# CR_Weather.net
KiCad netlist of a schematic drawn in EAGLE
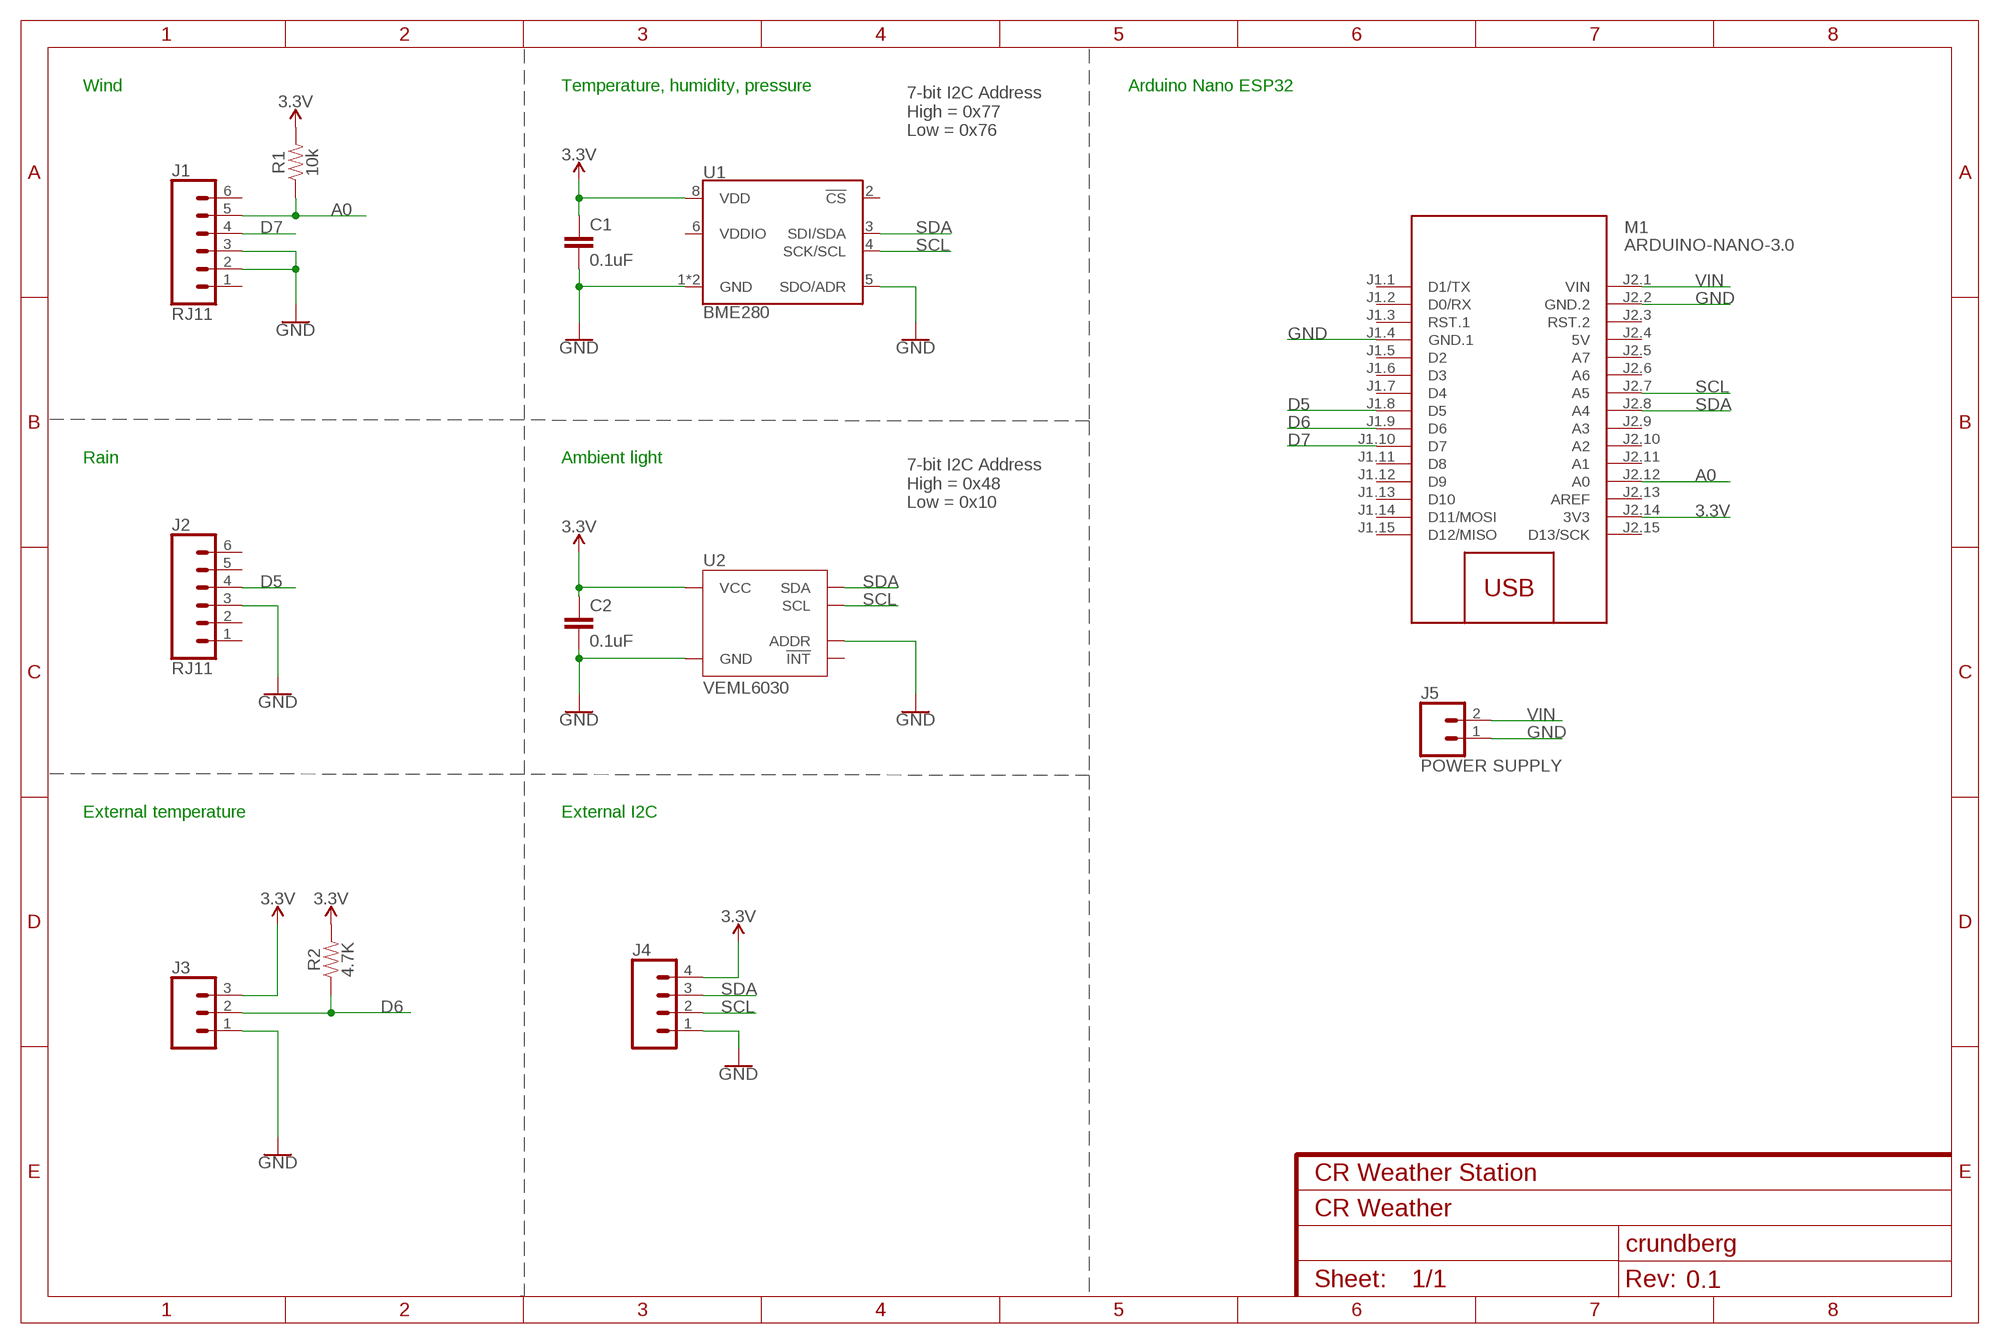
[diagram p0: schematic, sheet 1]

(export (version "E")
  (design (tool "Eeschema 10.0.6"))
  (components
    (comp (ref "C1")
      (value "0.1uF")
      (footprint "eagle-import:0402")
      (libsource (lib "eagle-import") (part "0.1UF-0402-6.3V-10%-X7R"))
    )
    (comp (ref "C2")
      (value "0.1uF")
      (footprint "eagle-import:0402")
      (libsource (lib "eagle-import") (part "0.1UF-0402-6.3V-10%-X7R"))
    )
    (comp (ref "J1")
      (value "RJ11")
      (footprint "eagle-import:RJ11-6")
      (libsource (lib "eagle-import") (part "RJ11-6"))
    )
    (comp (ref "J2")
      (value "RJ11")
      (footprint "eagle-import:RJ11-6")
      (libsource (lib "eagle-import") (part "RJ11-6"))
    )
    (comp (ref "J3")
      (value "CONN_03SCREW")
      (footprint "eagle-import:SCREWTERMINAL-3.5MM-3")
      (libsource (lib "eagle-import") (part "CONN_03SCREW"))
    )
    (comp (ref "J4")
      (value "CONN_04SCREW")
      (footprint "eagle-import:SCREWTERMINAL-3.5MM-4")
      (libsource (lib "eagle-import") (part "CONN_04SCREW"))
    )
    (comp (ref "J5")
      (value "POWER SUPPLY")
      (footprint "eagle-import:SCREWTERMINAL-3.5MM-2")
      (libsource (lib "eagle-import") (part "CONN_023.5MM"))
    )
    (comp (ref "M1")
      (value "ARDUINO-NANO-3.0")
      (footprint "eagle-import:ARDUINO-NANO-3.0")
      (libsource (lib "eagle-import") (part "ARDUINO-NANO-3.0"))
    )
    (comp (ref "R1")
      (value "10k")
      (footprint "eagle-import:1206")
      (libsource (lib "eagle-import") (part "RESISTOR1206"))
    )
    (comp (ref "R2")
      (value "4.7K")
      (footprint "eagle-import:1206")
      (libsource (lib "eagle-import") (part "RESISTOR1206"))
    )
    (comp (ref "U1")
      (value "BME280")
      (footprint "eagle-import:LGA-8-2.5X2.5")
      (libsource (lib "eagle-import") (part "BME280"))
    )
    (comp (ref "U2")
      (value "VEML6030")
      (footprint "eagle-import:VEML6030")
      (libsource (lib "eagle-import") (part "VEML6030"))
    )
  )
  (nets
    (net (code "1") (name "/5V") (class "Default")
      (node (ref "M1") (pin "J2.4") (pinfunction "5V_J2.4") (pintype "power_in"))
    )
    (net (code "2") (name "/A0") (class "Default")
      (node (ref "J1") (pin "5") (pinfunction "5_5") (pintype "passive"))
      (node (ref "M1") (pin "J2.12") (pinfunction "A0_J2.12") (pintype "bidirectional"))
      (node (ref "R1") (pin "1") (pinfunction "1_1") (pintype "passive"))
    )
    (net (code "3") (name "/D5") (class "Default")
      (node (ref "J2") (pin "4") (pinfunction "4_4") (pintype "passive"))
      (node (ref "M1") (pin "J1.8") (pinfunction "D5_J1.8") (pintype "bidirectional"))
    )
    (net (code "4") (name "/D6") (class "Default")
      (node (ref "J3") (pin "2") (pinfunction "2_2") (pintype "passive"))
      (node (ref "M1") (pin "J1.9") (pinfunction "D6_J1.9") (pintype "bidirectional"))
      (node (ref "R2") (pin "1") (pinfunction "1_1") (pintype "passive"))
    )
    (net (code "5") (name "/D7") (class "Default")
      (node (ref "J1") (pin "4") (pinfunction "4_4") (pintype "passive"))
      (node (ref "M1") (pin "J1.10") (pinfunction "D7_J1.10") (pintype "bidirectional"))
    )
    (net (code "6") (name "/SCL") (class "Default")
      (node (ref "J4") (pin "2") (pinfunction "2_2") (pintype "passive"))
      (node (ref "M1") (pin "J2.7") (pinfunction "A5_J2.7") (pintype "bidirectional"))
      (node (ref "U1") (pin "4") (pinfunction "SCK/SCL_4") (pintype "bidirectional"))
      (node (ref "U2") (pin "5") (pinfunction "SCL_5") (pintype "bidirectional"))
    )
    (net (code "7") (name "/SDA") (class "Default")
      (node (ref "J4") (pin "3") (pinfunction "3_3") (pintype "passive"))
      (node (ref "M1") (pin "J2.8") (pinfunction "A4_J2.8") (pintype "bidirectional"))
      (node (ref "U1") (pin "3") (pinfunction "SDI/SDA_3") (pintype "bidirectional"))
      (node (ref "U2") (pin "2") (pinfunction "SDA_2") (pintype "bidirectional"))
    )
    (net (code "8") (name "/VIN") (class "Default")
      (node (ref "J5") (pin "2") (pinfunction "2_2") (pintype "passive"))
      (node (ref "M1") (pin "J2.1") (pinfunction "VIN_J2.1") (pintype "power_in"))
    )
    (net (code "9") (name "3.3V") (class "Default")
      (node (ref "C1") (pin "1") (pinfunction "1_1") (pintype "passive"))
      (node (ref "C2") (pin "1") (pinfunction "1_1") (pintype "passive"))
      (node (ref "J3") (pin "3") (pinfunction "3_3") (pintype "passive"))
      (node (ref "J4") (pin "4") (pinfunction "4_4") (pintype "passive"))
      (node (ref "M1") (pin "J2.14") (pinfunction "3V3_J2.14") (pintype "power_in"))
      (node (ref "R1") (pin "2") (pinfunction "2_2") (pintype "passive"))
      (node (ref "R2") (pin "2") (pinfunction "2_2") (pintype "passive"))
      (node (ref "U1") (pin "8") (pinfunction "VDD_8") (pintype "bidirectional"))
      (node (ref "U2") (pin "6") (pinfunction "VCC_6") (pintype "power_in"))
    )
    (net (code "10") (name "GND") (class "Default")
      (node (ref "C1") (pin "2") (pinfunction "2_2") (pintype "passive"))
      (node (ref "C2") (pin "2") (pinfunction "2_2") (pintype "passive"))
      (node (ref "J1") (pin "2") (pinfunction "2_2") (pintype "passive"))
      (node (ref "J1") (pin "3") (pinfunction "3_3") (pintype "passive"))
      (node (ref "J2") (pin "3") (pinfunction "3_3") (pintype "passive"))
      (node (ref "J3") (pin "1") (pinfunction "1_1") (pintype "passive"))
      (node (ref "J4") (pin "1") (pinfunction "1_1") (pintype "passive"))
      (node (ref "J5") (pin "1") (pinfunction "1_1") (pintype "passive"))
      (node (ref "M1") (pin "J1.4") (pinfunction "GND.1_J1.4") (pintype "power_in"))
      (node (ref "M1") (pin "J2.2") (pinfunction "GND.2_J2.2") (pintype "power_in"))
      (node (ref "U1") (pin "1") (pinfunction "GND_1") (pintype "bidirectional"))
      (node (ref "U1") (pin "5") (pinfunction "SDO/ADR_5") (pintype "bidirectional"))
      (node (ref "U1") (pin "7") (pinfunction "GND_7") (pintype "bidirectional"))
      (node (ref "U2") (pin "1") (pinfunction "GND_1") (pintype "power_in"))
      (node (ref "U2") (pin "4") (pinfunction "ADDR_4") (pintype "bidirectional"))
    )
    (net (code "11") (name "unconnected-(J1-Pad1)") (class "Default")
      (node (ref "J1") (pin "1") (pinfunction "1_1") (pintype "passive"))
    )
    (net (code "12") (name "unconnected-(J1-Pad6)") (class "Default")
      (node (ref "J1") (pin "6") (pinfunction "6_6") (pintype "passive"))
    )
    (net (code "13") (name "unconnected-(J2-Pad1)") (class "Default")
      (node (ref "J2") (pin "1") (pinfunction "1_1") (pintype "passive"))
    )
    (net (code "14") (name "unconnected-(J2-Pad2)") (class "Default")
      (node (ref "J2") (pin "2") (pinfunction "2_2") (pintype "passive"))
    )
    (net (code "15") (name "unconnected-(J2-Pad5)") (class "Default")
      (node (ref "J2") (pin "5") (pinfunction "5_5") (pintype "passive"))
    )
    (net (code "16") (name "unconnected-(J2-Pad6)") (class "Default")
      (node (ref "J2") (pin "6") (pinfunction "6_6") (pintype "passive"))
    )
    (net (code "17") (name "unconnected-(M1-A1-PadJ2.11)") (class "Default")
      (node (ref "M1") (pin "J2.11") (pinfunction "A1_J2.11") (pintype "bidirectional"))
    )
    (net (code "18") (name "unconnected-(M1-A2-PadJ2.10)") (class "Default")
      (node (ref "M1") (pin "J2.10") (pinfunction "A2_J2.10") (pintype "bidirectional"))
    )
    (net (code "19") (name "unconnected-(M1-A3-PadJ2.9)") (class "Default")
      (node (ref "M1") (pin "J2.9") (pinfunction "A3_J2.9") (pintype "bidirectional"))
    )
    (net (code "20") (name "unconnected-(M1-A6-PadJ2.6)") (class "Default")
      (node (ref "M1") (pin "J2.6") (pinfunction "A6_J2.6") (pintype "bidirectional"))
    )
    (net (code "21") (name "unconnected-(M1-A7-PadJ2.5)") (class "Default")
      (node (ref "M1") (pin "J2.5") (pinfunction "A7_J2.5") (pintype "bidirectional"))
    )
    (net (code "22") (name "unconnected-(M1-AREF-PadJ2.13)") (class "Default")
      (node (ref "M1") (pin "J2.13") (pinfunction "AREF_J2.13") (pintype "bidirectional"))
    )
    (net (code "23") (name "unconnected-(M1-D0{slash}RX-PadJ1.2)") (class "Default")
      (node (ref "M1") (pin "J1.2") (pinfunction "D0/RX_J1.2") (pintype "bidirectional"))
    )
    (net (code "24") (name "unconnected-(M1-D1{slash}TX-PadJ1.1)") (class "Default")
      (node (ref "M1") (pin "J1.1") (pinfunction "D1/TX_J1.1") (pintype "bidirectional"))
    )
    (net (code "25") (name "unconnected-(M1-D2-PadJ1.5)") (class "Default")
      (node (ref "M1") (pin "J1.5") (pinfunction "D2_J1.5") (pintype "bidirectional"))
    )
    (net (code "26") (name "unconnected-(M1-D3-PadJ1.6)") (class "Default")
      (node (ref "M1") (pin "J1.6") (pinfunction "D3_J1.6") (pintype "bidirectional"))
    )
    (net (code "27") (name "unconnected-(M1-D4-PadJ1.7)") (class "Default")
      (node (ref "M1") (pin "J1.7") (pinfunction "D4_J1.7") (pintype "bidirectional"))
    )
    (net (code "28") (name "unconnected-(M1-D8-PadJ1.11)") (class "Default")
      (node (ref "M1") (pin "J1.11") (pinfunction "D8_J1.11") (pintype "bidirectional"))
    )
    (net (code "29") (name "unconnected-(M1-D9-PadJ1.12)") (class "Default")
      (node (ref "M1") (pin "J1.12") (pinfunction "D9_J1.12") (pintype "bidirectional"))
    )
    (net (code "30") (name "unconnected-(M1-D10-PadJ1.13)") (class "Default")
      (node (ref "M1") (pin "J1.13") (pinfunction "D10_J1.13") (pintype "bidirectional"))
    )
    (net (code "31") (name "unconnected-(M1-D11{slash}MOSI-PadJ1.14)") (class "Default")
      (node (ref "M1") (pin "J1.14") (pinfunction "D11/MOSI_J1.14") (pintype "bidirectional"))
    )
    (net (code "32") (name "unconnected-(M1-D12{slash}MISO-PadJ1.15)") (class "Default")
      (node (ref "M1") (pin "J1.15") (pinfunction "D12/MISO_J1.15") (pintype "bidirectional"))
    )
    (net (code "33") (name "unconnected-(M1-D13{slash}SCK-PadJ2.15)") (class "Default")
      (node (ref "M1") (pin "J2.15") (pinfunction "D13/SCK_J2.15") (pintype "bidirectional"))
    )
    (net (code "34") (name "unconnected-(M1-RST.1-PadJ1.3)") (class "Default")
      (node (ref "M1") (pin "J1.3") (pinfunction "RST.1_J1.3") (pintype "bidirectional"))
    )
    (net (code "35") (name "unconnected-(M1-RST.2-PadJ2.3)") (class "Default")
      (node (ref "M1") (pin "J2.3") (pinfunction "RST.2_J2.3") (pintype "bidirectional"))
    )
    (net (code "36") (name "unconnected-(U1-VDDIO-Pad6)") (class "Default")
      (node (ref "U1") (pin "6") (pinfunction "VDDIO_6") (pintype "bidirectional"))
    )
    (net (code "37") (name "unconnected-(U1-~{CS}-Pad2)") (class "Default")
      (node (ref "U1") (pin "2") (pinfunction "~{CS}_2") (pintype "bidirectional"))
    )
    (net (code "38") (name "unconnected-(U2-~{INT}-Pad3)") (class "Default")
      (node (ref "U2") (pin "3") (pinfunction "~{INT}_3") (pintype "output"))
    )
  )
)
